# LPCB235_-_RM48_-_SERIAL.net
KiCad netlist of a schematic drawn in Altium Designer
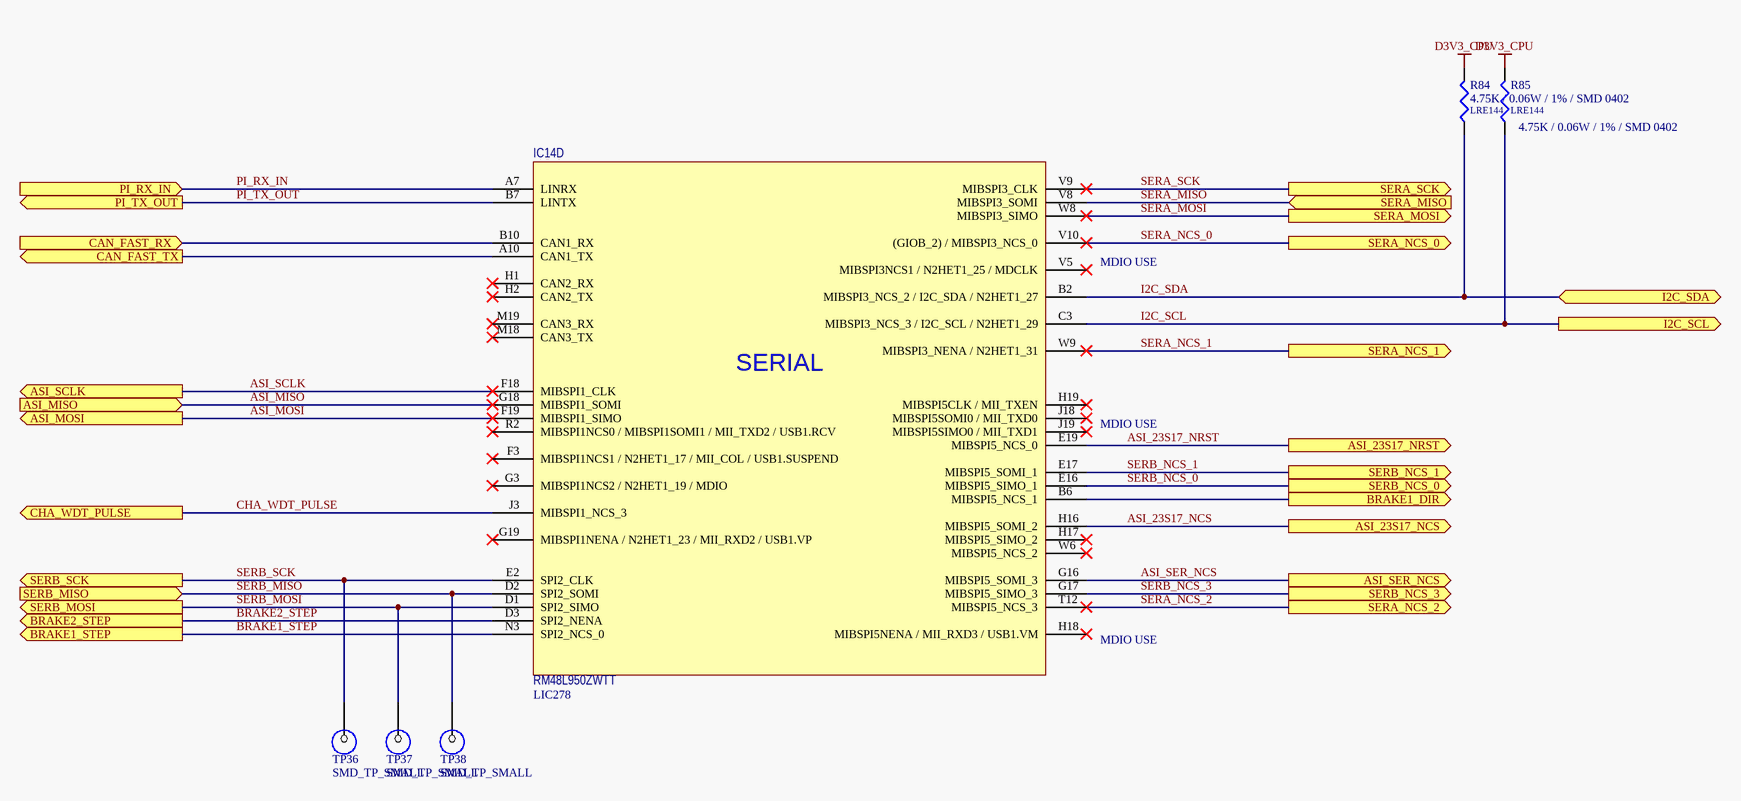
[diagram p0: LPCB235 - RM48 - SERIAL.SchDoc]

(export (version "E")
  (design (tool "Eeschema 10.0.6"))
  (components
    (comp (ref "IC14")
      (value "RM48L950ZWTT")
      (footprint "LFP054__ZWT (S-PBGA-N337)")
      (description "IC, CPU, RM48 Safety CPU, SMD NFBGA337 [LIC278]")
      (fields (field (name "LDL_NUMBER") "LIC278"))
      (libsource (lib "LDL_Semiconductors") (part "RM48L950ZWTT"))
    )
    (comp (ref "R84")
      (value "4.75K / 0.06W / 1% / SMD 0402")
      (footprint "LFP030__CR1005-0402-IPC7351")
      (description "Resistor, Ceramic Chip, 4.75K, 0.0625W, 1%, SMD 0402 [LRE144]")
      (fields (field (name "LDL_NUMBER") "LRE144"))
      (libsource (lib "LDL_Resistors") (part "4.75K / 0.06W / 1% / SMD 0402"))
    )
    (comp (ref "R85")
      (value "4.75K / 0.06W / 1% / SMD 0402")
      (footprint "LFP030__CR1005-0402-IPC7351")
      (description "Resistor, Ceramic Chip, 4.75K, 0.0625W, 1%, SMD 0402 [LRE144]")
      (fields (field (name "LDL_NUMBER") "LRE144"))
      (libsource (lib "LDL_Resistors") (part "4.75K / 0.06W / 1% / SMD 0402"))
    )
    (comp (ref "TP36")
      (value "SMD_TP_SMALL")
      (footprint "SMD-TP-SMALL")
      (description "SMD Test Point")
      (libsource (lib "LDL_Connectors") (part "SMD_TP_SMALL"))
    )
    (comp (ref "TP37")
      (value "SMD_TP_SMALL")
      (footprint "SMD-TP-SMALL")
      (description "SMD Test Point")
      (libsource (lib "LDL_Connectors") (part "SMD_TP_SMALL"))
    )
    (comp (ref "TP38")
      (value "SMD_TP_SMALL")
      (footprint "SMD-TP-SMALL")
      (description "SMD Test Point")
      (libsource (lib "LDL_Connectors") (part "SMD_TP_SMALL"))
    )
  )
  (nets
    (net (code "1") (name "/ASI_23S17_NCS") (class "Default")
      (node (ref "IC14") (pin "H16") (pinfunction "MIBSPI5_SOMI_2_H16") (pintype "passive"))
    )
    (net (code "2") (name "/ASI_23S17_NRST") (class "Default")
      (node (ref "IC14") (pin "E19") (pinfunction "MIBSPI5_NCS_0_E19") (pintype "passive"))
    )
    (net (code "3") (name "/ASI_MISO") (class "Default")
      (node (ref "IC14") (pin "G18") (pinfunction "MIBSPI1_SOMI_G18") (pintype "passive+no_connect"))
    )
    (net (code "4") (name "/ASI_MOSI") (class "Default")
      (node (ref "IC14") (pin "F19") (pinfunction "MIBSPI1_SIMO_F19") (pintype "passive+no_connect"))
    )
    (net (code "5") (name "/ASI_SCLK") (class "Default")
      (node (ref "IC14") (pin "F18") (pinfunction "MIBSPI1_CLK_F18") (pintype "passive+no_connect"))
    )
    (net (code "6") (name "/ASI_SER_NCS") (class "Default")
      (node (ref "IC14") (pin "G16") (pinfunction "MIBSPI5_SOMI_3_G16") (pintype "passive"))
    )
    (net (code "7") (name "/BRAKE1_DIR") (class "Default")
      (node (ref "IC14") (pin "B6") (pinfunction "MIBSPI5_NCS_1_B6") (pintype "passive"))
    )
    (net (code "8") (name "/BRAKE1_STEP") (class "Default")
      (node (ref "IC14") (pin "N3") (pinfunction "SPI2_NCS_0_N3") (pintype "passive"))
    )
    (net (code "9") (name "/BRAKE2_STEP") (class "Default")
      (node (ref "IC14") (pin "D3") (pinfunction "SPI2_NENA_D3") (pintype "passive"))
    )
    (net (code "10") (name "/CAN_FAST_RX") (class "Default")
      (node (ref "IC14") (pin "B10") (pinfunction "CAN1_RX_B10") (pintype "passive"))
    )
    (net (code "11") (name "/CAN_FAST_TX") (class "Default")
      (node (ref "IC14") (pin "A10") (pinfunction "CAN1_TX_A10") (pintype "passive"))
    )
    (net (code "12") (name "/CHA_WDT_PULSE") (class "Default")
      (node (ref "IC14") (pin "J3") (pinfunction "MIBSPI1_NCS_3_J3") (pintype "passive"))
    )
    (net (code "13") (name "/I2C_SCL") (class "Default")
      (node (ref "IC14") (pin "C3") (pinfunction "MIBSPI3_NCS_3_/_I2C_SCL_/_N2HET1_29_C3") (pintype "passive"))
      (node (ref "R85") (pin "1") (pintype "passive"))
    )
    (net (code "14") (name "/I2C_SDA") (class "Default")
      (node (ref "IC14") (pin "B2") (pinfunction "MIBSPI3_NCS_2_/_I2C_SDA_/_N2HET1_27_B2") (pintype "passive"))
      (node (ref "R84") (pin "1") (pintype "passive"))
    )
    (net (code "15") (name "/PI_RX_IN") (class "Default")
      (node (ref "IC14") (pin "A7") (pinfunction "LINRX_A7") (pintype "passive"))
    )
    (net (code "16") (name "/PI_TX_OUT") (class "Default")
      (node (ref "IC14") (pin "B7") (pinfunction "LINTX_B7") (pintype "passive"))
    )
    (net (code "17") (name "/SERA_MISO") (class "Default")
      (node (ref "IC14") (pin "V8") (pinfunction "MIBSPI3_SOMI_V8") (pintype "passive"))
    )
    (net (code "18") (name "/SERA_MOSI") (class "Default")
      (node (ref "IC14") (pin "W8") (pinfunction "MIBSPI3_SIMO_W8") (pintype "passive+no_connect"))
    )
    (net (code "19") (name "/SERA_NCS_0") (class "Default")
      (node (ref "IC14") (pin "V10") (pinfunction "(GIOB_2)_/_MIBSPI3_NCS_0_V10") (pintype "passive+no_connect"))
    )
    (net (code "20") (name "/SERA_NCS_1") (class "Default")
      (node (ref "IC14") (pin "W9") (pinfunction "MIBSPI3_NENA_/_N2HET1_31_W9") (pintype "passive+no_connect"))
    )
    (net (code "21") (name "/SERA_NCS_2") (class "Default")
      (node (ref "IC14") (pin "T12") (pinfunction "MIBSPI5_NCS_3_T12") (pintype "passive+no_connect"))
    )
    (net (code "22") (name "/SERA_SCK") (class "Default")
      (node (ref "IC14") (pin "V9") (pinfunction "MIBSPI3_CLK_V9") (pintype "passive+no_connect"))
    )
    (net (code "23") (name "/SERB_MISO") (class "Default")
      (node (ref "IC14") (pin "D2") (pinfunction "SPI2_SOMI_D2") (pintype "passive"))
      (node (ref "TP38") (pin "1") (pintype "passive"))
    )
    (net (code "24") (name "/SERB_MOSI") (class "Default")
      (node (ref "IC14") (pin "D1") (pinfunction "SPI2_SIMO_D1") (pintype "passive"))
      (node (ref "TP37") (pin "1") (pintype "passive"))
    )
    (net (code "25") (name "/SERB_NCS_0") (class "Default")
      (node (ref "IC14") (pin "E16") (pinfunction "MIBSPI5_SIMO_1_E16") (pintype "passive"))
    )
    (net (code "26") (name "/SERB_NCS_1") (class "Default")
      (node (ref "IC14") (pin "E17") (pinfunction "MIBSPI5_SOMI_1_E17") (pintype "passive"))
    )
    (net (code "27") (name "/SERB_NCS_3") (class "Default")
      (node (ref "IC14") (pin "G17") (pinfunction "MIBSPI5_SIMO_3_G17") (pintype "passive"))
    )
    (net (code "28") (name "/SERB_SCK") (class "Default")
      (node (ref "IC14") (pin "E2") (pinfunction "SPI2_CLK_E2") (pintype "passive"))
      (node (ref "TP36") (pin "1") (pintype "passive"))
    )
    (net (code "29") (name "D3V3_CPU") (class "Default")
      (node (ref "R84") (pin "2") (pintype "passive"))
      (node (ref "R85") (pin "2") (pintype "passive"))
    )
    (net (code "30") (name "unconnected-(IC14D-CAN2_RX-PadH1)") (class "Default")
      (node (ref "IC14") (pin "H1") (pinfunction "CAN2_RX_H1") (pintype "passive+no_connect"))
    )
    (net (code "31") (name "unconnected-(IC14D-CAN2_TX-PadH2)") (class "Default")
      (node (ref "IC14") (pin "H2") (pinfunction "CAN2_TX_H2") (pintype "passive+no_connect"))
    )
    (net (code "32") (name "unconnected-(IC14D-CAN3_RX-PadM19)") (class "Default")
      (node (ref "IC14") (pin "M19") (pinfunction "CAN3_RX_M19") (pintype "passive+no_connect"))
    )
    (net (code "33") (name "unconnected-(IC14D-CAN3_TX-PadM18)") (class "Default")
      (node (ref "IC14") (pin "M18") (pinfunction "CAN3_TX_M18") (pintype "passive+no_connect"))
    )
    (net (code "34") (name "unconnected-(IC14D-MIBSPI1NCS0_{slash}_MIBSPI1SOMI1_{slash}_MII_TXD2_{slash}_USB1.RCV-PadR2)") (class "Default")
      (node (ref "IC14") (pin "R2") (pinfunction "MIBSPI1NCS0_/_MIBSPI1SOMI1_/_MII_TXD2_/_USB1.RCV_R2") (pintype "passive+no_connect"))
    )
    (net (code "35") (name "unconnected-(IC14D-MIBSPI1NCS1_{slash}_N2HET1_17_{slash}_MII_COL_{slash}_USB1.SUSPEND-PadF3)") (class "Default")
      (node (ref "IC14") (pin "F3") (pinfunction "MIBSPI1NCS1_/_N2HET1_17_/_MII_COL_/_USB1.SUSPEND_F3") (pintype "passive+no_connect"))
    )
    (net (code "36") (name "unconnected-(IC14D-MIBSPI1NCS2_{slash}_N2HET1_19_{slash}_MDIO-PadG3)") (class "Default")
      (node (ref "IC14") (pin "G3") (pinfunction "MIBSPI1NCS2_/_N2HET1_19_/_MDIO_G3") (pintype "passive+no_connect"))
    )
    (net (code "37") (name "unconnected-(IC14D-MIBSPI1NENA_{slash}_N2HET1_23_{slash}_MII_RXD2_{slash}_USB1.VP-PadG19)") (class "Default")
      (node (ref "IC14") (pin "G19") (pinfunction "MIBSPI1NENA_/_N2HET1_23_/_MII_RXD2_/_USB1.VP_G19") (pintype "passive+no_connect"))
    )
    (net (code "38") (name "unconnected-(IC14D-MIBSPI3NCS1_{slash}_N2HET1_25_{slash}_MDCLK-PadV5)") (class "Default")
      (node (ref "IC14") (pin "V5") (pinfunction "MIBSPI3NCS1_/_N2HET1_25_/_MDCLK_V5") (pintype "passive+no_connect"))
    )
    (net (code "39") (name "unconnected-(IC14D-MIBSPI5CLK_{slash}_MII_TXEN-PadH19)") (class "Default")
      (node (ref "IC14") (pin "H19") (pinfunction "MIBSPI5CLK_/_MII_TXEN_H19") (pintype "passive+no_connect"))
    )
    (net (code "40") (name "unconnected-(IC14D-MIBSPI5NENA_{slash}_MII_RXD3_{slash}_USB1.VM-PadH18)") (class "Default")
      (node (ref "IC14") (pin "H18") (pinfunction "MIBSPI5NENA_/_MII_RXD3_/_USB1.VM_H18") (pintype "passive+no_connect"))
    )
    (net (code "41") (name "unconnected-(IC14D-MIBSPI5SIMO0_{slash}_MII_TXD1-PadJ19)") (class "Default")
      (node (ref "IC14") (pin "J19") (pinfunction "MIBSPI5SIMO0_/_MII_TXD1_J19") (pintype "passive+no_connect"))
    )
    (net (code "42") (name "unconnected-(IC14D-MIBSPI5SOMI0_{slash}_MII_TXD0-PadJ18)") (class "Default")
      (node (ref "IC14") (pin "J18") (pinfunction "MIBSPI5SOMI0_/_MII_TXD0_J18") (pintype "passive+no_connect"))
    )
    (net (code "43") (name "unconnected-(IC14D-MIBSPI5_NCS_2-PadW6)") (class "Default")
      (node (ref "IC14") (pin "W6") (pinfunction "MIBSPI5_NCS_2_W6") (pintype "passive+no_connect"))
    )
    (net (code "44") (name "unconnected-(IC14D-MIBSPI5_SIMO_2-PadH17)") (class "Default")
      (node (ref "IC14") (pin "H17") (pinfunction "MIBSPI5_SIMO_2_H17") (pintype "passive+no_connect"))
    )
  )
)
